# Adafruit_NeoPixel_Ring_24_rev_C.net
KiCad netlist of a schematic drawn in EAGLE
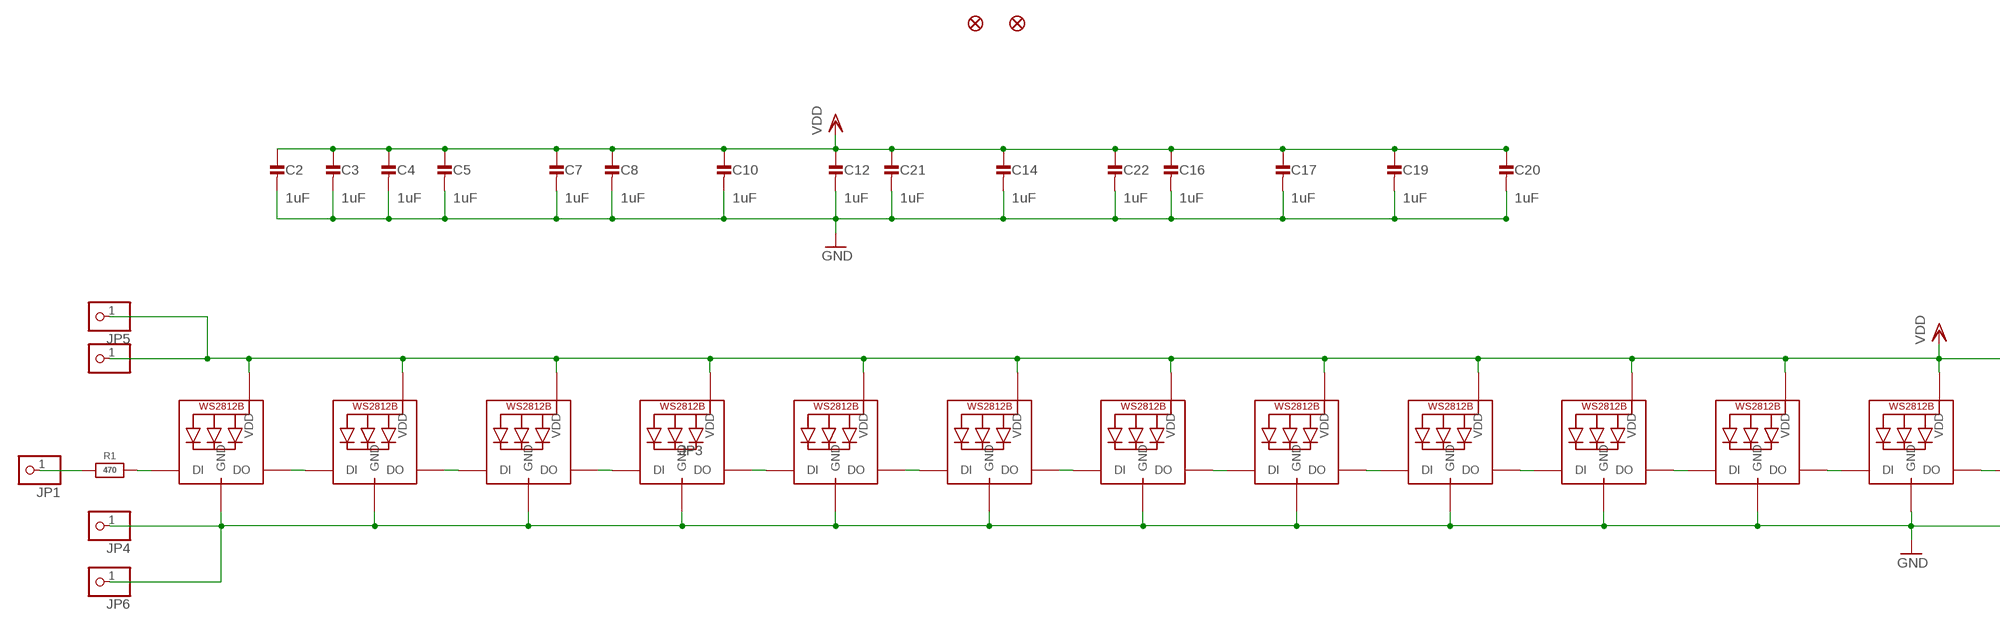
[diagram p0: schematic, sheet 1, part 1 of 2]
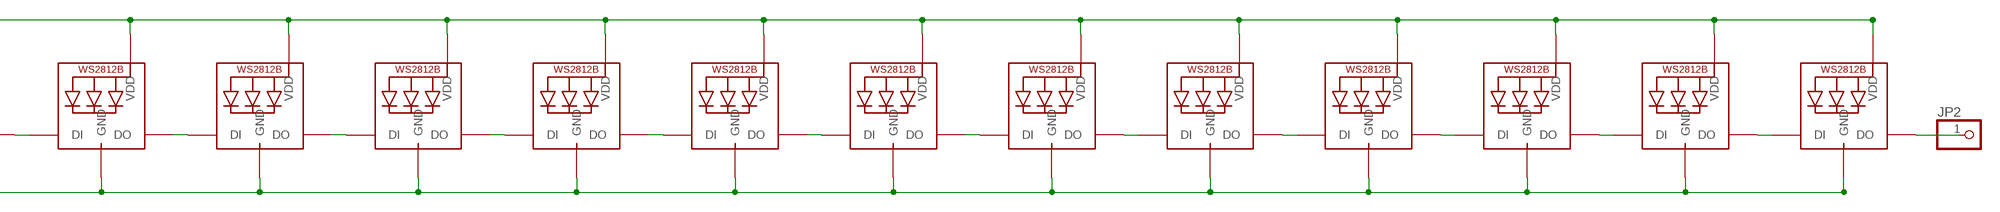
[diagram p1: schematic, sheet 1, part 2 of 2]

(export (version "E")
  (design (tool "Eeschema 10.0.6"))
  (components
    (comp (ref "C2")
      (value "1uF")
      (footprint "eagle-import:0603-NO")
      (libsource (lib "eagle-import") (part "CAP_CERAMIC0603_NO"))
    )
    (comp (ref "C3")
      (value "1uF")
      (footprint "eagle-import:0603-NO")
      (libsource (lib "eagle-import") (part "CAP_CERAMIC0603_NO"))
    )
    (comp (ref "C4")
      (value "1uF")
      (footprint "eagle-import:0603-NO")
      (libsource (lib "eagle-import") (part "CAP_CERAMIC0603_NO"))
    )
    (comp (ref "C5")
      (value "1uF")
      (footprint "eagle-import:0603-NO")
      (libsource (lib "eagle-import") (part "CAP_CERAMIC0603_NO"))
    )
    (comp (ref "C7")
      (value "1uF")
      (footprint "eagle-import:0603-NO")
      (libsource (lib "eagle-import") (part "CAP_CERAMIC0603_NO"))
    )
    (comp (ref "C8")
      (value "1uF")
      (footprint "eagle-import:0603-NO")
      (libsource (lib "eagle-import") (part "CAP_CERAMIC0603_NO"))
    )
    (comp (ref "C10")
      (value "1uF")
      (footprint "eagle-import:0603-NO")
      (libsource (lib "eagle-import") (part "CAP_CERAMIC0603_NO"))
    )
    (comp (ref "C12")
      (value "1uF")
      (footprint "eagle-import:0603-NO")
      (libsource (lib "eagle-import") (part "CAP_CERAMIC0603_NO"))
    )
    (comp (ref "C14")
      (value "1uF")
      (footprint "eagle-import:0603-NO")
      (libsource (lib "eagle-import") (part "CAP_CERAMIC0603_NO"))
    )
    (comp (ref "C16")
      (value "1uF")
      (footprint "eagle-import:0603-NO")
      (libsource (lib "eagle-import") (part "CAP_CERAMIC0603_NO"))
    )
    (comp (ref "C17")
      (value "1uF")
      (footprint "eagle-import:0603-NO")
      (libsource (lib "eagle-import") (part "CAP_CERAMIC0603_NO"))
    )
    (comp (ref "C19")
      (value "1uF")
      (footprint "eagle-import:0603-NO")
      (libsource (lib "eagle-import") (part "CAP_CERAMIC0603_NO"))
    )
    (comp (ref "C20")
      (value "1uF")
      (footprint "eagle-import:0603-NO")
      (libsource (lib "eagle-import") (part "CAP_CERAMIC0603_NO"))
    )
    (comp (ref "C21")
      (value "1uF")
      (footprint "eagle-import:0603-NO")
      (libsource (lib "eagle-import") (part "CAP_CERAMIC0603_NO"))
    )
    (comp (ref "C22")
      (value "1uF")
      (footprint "eagle-import:0603-NO")
      (libsource (lib "eagle-import") (part "CAP_CERAMIC0603_NO"))
    )
    (comp (ref "FID1")
      (value "FIDUCIAL")
      (footprint "eagle-import:FIDUCIAL_1MM")
      (libsource (lib "eagle-import") (part "FIDUCIAL_1MM"))
    )
    (comp (ref "FID2")
      (value "FIDUCIAL")
      (footprint "eagle-import:FIDUCIAL_1MM")
      (libsource (lib "eagle-import") (part "FIDUCIAL_1MM"))
    )
    (comp (ref "JP1")
      (value "PINHD-1X1CB")
      (footprint "eagle-import:1X01-CLEANBIG")
      (libsource (lib "eagle-import") (part "PINHD-1X1CB"))
    )
    (comp (ref "JP2")
      (value "PINHD-1X1CB")
      (footprint "eagle-import:1X01-CLEANBIG")
      (libsource (lib "eagle-import") (part "PINHD-1X1CB"))
    )
    (comp (ref "JP3")
      (value "PINHD-1X1CB")
      (footprint "eagle-import:1X01-CLEANBIG")
      (libsource (lib "eagle-import") (part "PINHD-1X1CB"))
    )
    (comp (ref "JP4")
      (value "PINHD-1X1CB")
      (footprint "eagle-import:1X01-CLEANBIG")
      (libsource (lib "eagle-import") (part "PINHD-1X1CB"))
    )
    (comp (ref "JP5")
      (value "PINHD-1X1CB")
      (footprint "eagle-import:1X01-CLEANBIG")
      (libsource (lib "eagle-import") (part "PINHD-1X1CB"))
    )
    (comp (ref "JP6")
      (value "PINHD-1X1CB")
      (footprint "eagle-import:1X01-CLEANBIG")
      (libsource (lib "eagle-import") (part "PINHD-1X1CB"))
    )
    (comp (ref "LED1")
      (value "WS2812B_5050N")
      (footprint "eagle-import:WS2812B-NARROW")
      (libsource (lib "eagle-import") (part "WS2812B_5050N"))
    )
    (comp (ref "LED2")
      (value "WS2812B_5050N")
      (footprint "eagle-import:WS2812B-NARROW")
      (libsource (lib "eagle-import") (part "WS2812B_5050N"))
    )
    (comp (ref "LED3")
      (value "WS2812B_5050N")
      (footprint "eagle-import:WS2812B-NARROW")
      (libsource (lib "eagle-import") (part "WS2812B_5050N"))
    )
    (comp (ref "LED4")
      (value "WS2812B_5050N")
      (footprint "eagle-import:WS2812B-NARROW")
      (libsource (lib "eagle-import") (part "WS2812B_5050N"))
    )
    (comp (ref "LED5")
      (value "WS2812B_5050N")
      (footprint "eagle-import:WS2812B-NARROW")
      (libsource (lib "eagle-import") (part "WS2812B_5050N"))
    )
    (comp (ref "LED6")
      (value "WS2812B_5050N")
      (footprint "eagle-import:WS2812B-NARROW")
      (libsource (lib "eagle-import") (part "WS2812B_5050N"))
    )
    (comp (ref "LED7")
      (value "WS2812B_5050N")
      (footprint "eagle-import:WS2812B-NARROW")
      (libsource (lib "eagle-import") (part "WS2812B_5050N"))
    )
    (comp (ref "LED8")
      (value "WS2812B_5050N")
      (footprint "eagle-import:WS2812B-NARROW")
      (libsource (lib "eagle-import") (part "WS2812B_5050N"))
    )
    (comp (ref "LED9")
      (value "WS2812B_5050N")
      (footprint "eagle-import:WS2812B-NARROW")
      (libsource (lib "eagle-import") (part "WS2812B_5050N"))
    )
    (comp (ref "LED10")
      (value "WS2812B_5050N")
      (footprint "eagle-import:WS2812B-NARROW")
      (libsource (lib "eagle-import") (part "WS2812B_5050N"))
    )
    (comp (ref "LED11")
      (value "WS2812B_5050N")
      (footprint "eagle-import:WS2812B-NARROW")
      (libsource (lib "eagle-import") (part "WS2812B_5050N"))
    )
    (comp (ref "LED12")
      (value "WS2812B_5050N")
      (footprint "eagle-import:WS2812B-NARROW")
      (libsource (lib "eagle-import") (part "WS2812B_5050N"))
    )
    (comp (ref "LED13")
      (value "WS2812B_5050N")
      (footprint "eagle-import:WS2812B-NARROW")
      (libsource (lib "eagle-import") (part "WS2812B_5050N"))
    )
    (comp (ref "LED14")
      (value "WS2812B_5050N")
      (footprint "eagle-import:WS2812B-NARROW")
      (libsource (lib "eagle-import") (part "WS2812B_5050N"))
    )
    (comp (ref "LED15")
      (value "WS2812B_5050N")
      (footprint "eagle-import:WS2812B-NARROW")
      (libsource (lib "eagle-import") (part "WS2812B_5050N"))
    )
    (comp (ref "LED16")
      (value "WS2812B_5050N")
      (footprint "eagle-import:WS2812B-NARROW")
      (libsource (lib "eagle-import") (part "WS2812B_5050N"))
    )
    (comp (ref "LED17")
      (value "WS2812B_5050N")
      (footprint "eagle-import:WS2812B-NARROW")
      (libsource (lib "eagle-import") (part "WS2812B_5050N"))
    )
    (comp (ref "LED18")
      (value "WS2812B_5050N")
      (footprint "eagle-import:WS2812B-NARROW")
      (libsource (lib "eagle-import") (part "WS2812B_5050N"))
    )
    (comp (ref "LED19")
      (value "WS2812B_5050N")
      (footprint "eagle-import:WS2812B-NARROW")
      (libsource (lib "eagle-import") (part "WS2812B_5050N"))
    )
    (comp (ref "LED20")
      (value "WS2812B_5050N")
      (footprint "eagle-import:WS2812B-NARROW")
      (libsource (lib "eagle-import") (part "WS2812B_5050N"))
    )
    (comp (ref "LED21")
      (value "WS2812B_5050N")
      (footprint "eagle-import:WS2812B-NARROW")
      (libsource (lib "eagle-import") (part "WS2812B_5050N"))
    )
    (comp (ref "LED22")
      (value "WS2812B_5050N")
      (footprint "eagle-import:WS2812B-NARROW")
      (libsource (lib "eagle-import") (part "WS2812B_5050N"))
    )
    (comp (ref "LED23")
      (value "WS2812B_5050N")
      (footprint "eagle-import:WS2812B-NARROW")
      (libsource (lib "eagle-import") (part "WS2812B_5050N"))
    )
    (comp (ref "LED24")
      (value "WS2812B_5050N")
      (footprint "eagle-import:WS2812B-NARROW")
      (libsource (lib "eagle-import") (part "WS2812B_5050N"))
    )
    (comp (ref "R1")
      (value "470")
      (footprint "eagle-import:0603-NO")
      (libsource (lib "eagle-import") (part "RESISTOR_0603_NOOUT"))
    )
  )
  (nets
    (net (code "1") (name "GND") (class "Default")
      (node (ref "C10") (pin "2") (pinfunction "2_2") (pintype "passive"))
      (node (ref "C12") (pin "2") (pinfunction "2_2") (pintype "passive"))
      (node (ref "C14") (pin "2") (pinfunction "2_2") (pintype "passive"))
      (node (ref "C16") (pin "2") (pinfunction "2_2") (pintype "passive"))
      (node (ref "C17") (pin "2") (pinfunction "2_2") (pintype "passive"))
      (node (ref "C19") (pin "2") (pinfunction "2_2") (pintype "passive"))
      (node (ref "C2") (pin "2") (pinfunction "2_2") (pintype "passive"))
      (node (ref "C20") (pin "2") (pinfunction "2_2") (pintype "passive"))
      (node (ref "C21") (pin "2") (pinfunction "2_2") (pintype "passive"))
      (node (ref "C22") (pin "2") (pinfunction "2_2") (pintype "passive"))
      (node (ref "C3") (pin "2") (pinfunction "2_2") (pintype "passive"))
      (node (ref "C4") (pin "2") (pinfunction "2_2") (pintype "passive"))
      (node (ref "C5") (pin "2") (pinfunction "2_2") (pintype "passive"))
      (node (ref "C7") (pin "2") (pinfunction "2_2") (pintype "passive"))
      (node (ref "C8") (pin "2") (pinfunction "2_2") (pintype "passive"))
      (node (ref "JP4") (pin "1") (pinfunction "1_1") (pintype "passive"))
      (node (ref "JP6") (pin "1") (pinfunction "1_1") (pintype "passive"))
      (node (ref "LED1") (pin "3-GND") (pinfunction "GND_3-GND") (pintype "power_in"))
      (node (ref "LED10") (pin "3-GND") (pinfunction "GND_3-GND") (pintype "power_in"))
      (node (ref "LED11") (pin "3-GND") (pinfunction "GND_3-GND") (pintype "power_in"))
      (node (ref "LED12") (pin "3-GND") (pinfunction "GND_3-GND") (pintype "power_in"))
      (node (ref "LED13") (pin "3-GND") (pinfunction "GND_3-GND") (pintype "power_in"))
      (node (ref "LED14") (pin "3-GND") (pinfunction "GND_3-GND") (pintype "power_in"))
      (node (ref "LED15") (pin "3-GND") (pinfunction "GND_3-GND") (pintype "power_in"))
      (node (ref "LED16") (pin "3-GND") (pinfunction "GND_3-GND") (pintype "power_in"))
      (node (ref "LED17") (pin "3-GND") (pinfunction "GND_3-GND") (pintype "power_in"))
      (node (ref "LED18") (pin "3-GND") (pinfunction "GND_3-GND") (pintype "power_in"))
      (node (ref "LED19") (pin "3-GND") (pinfunction "GND_3-GND") (pintype "power_in"))
      (node (ref "LED2") (pin "3-GND") (pinfunction "GND_3-GND") (pintype "power_in"))
      (node (ref "LED20") (pin "3-GND") (pinfunction "GND_3-GND") (pintype "power_in"))
      (node (ref "LED21") (pin "3-GND") (pinfunction "GND_3-GND") (pintype "power_in"))
      (node (ref "LED22") (pin "3-GND") (pinfunction "GND_3-GND") (pintype "power_in"))
      (node (ref "LED23") (pin "3-GND") (pinfunction "GND_3-GND") (pintype "power_in"))
      (node (ref "LED24") (pin "3-GND") (pinfunction "GND_3-GND") (pintype "power_in"))
      (node (ref "LED3") (pin "3-GND") (pinfunction "GND_3-GND") (pintype "power_in"))
      (node (ref "LED4") (pin "3-GND") (pinfunction "GND_3-GND") (pintype "power_in"))
      (node (ref "LED5") (pin "3-GND") (pinfunction "GND_3-GND") (pintype "power_in"))
      (node (ref "LED6") (pin "3-GND") (pinfunction "GND_3-GND") (pintype "power_in"))
      (node (ref "LED7") (pin "3-GND") (pinfunction "GND_3-GND") (pintype "power_in"))
      (node (ref "LED8") (pin "3-GND") (pinfunction "GND_3-GND") (pintype "power_in"))
      (node (ref "LED9") (pin "3-GND") (pinfunction "GND_3-GND") (pintype "power_in"))
    )
    (net (code "2") (name "Net-(JP1-Pad1)") (class "Default")
      (node (ref "JP1") (pin "1") (pinfunction "1_1") (pintype "passive"))
      (node (ref "R1") (pin "1") (pinfunction "1_1") (pintype "passive"))
    )
    (net (code "3") (name "Net-(LED1-DI)") (class "Default")
      (node (ref "LED1") (pin "4-DIN") (pinfunction "DI_4-DIN") (pintype "input"))
      (node (ref "R1") (pin "2") (pinfunction "2_2") (pintype "passive"))
    )
    (net (code "4") (name "Net-(LED1-DO)") (class "Default")
      (node (ref "LED1") (pin "2-DOUT") (pinfunction "DO_2-DOUT") (pintype "output"))
      (node (ref "LED2") (pin "4-DIN") (pinfunction "DI_4-DIN") (pintype "input"))
    )
    (net (code "5") (name "Net-(LED2-DO)") (class "Default")
      (node (ref "LED2") (pin "2-DOUT") (pinfunction "DO_2-DOUT") (pintype "output"))
      (node (ref "LED3") (pin "4-DIN") (pinfunction "DI_4-DIN") (pintype "input"))
    )
    (net (code "6") (name "Net-(LED3-DO)") (class "Default")
      (node (ref "LED3") (pin "2-DOUT") (pinfunction "DO_2-DOUT") (pintype "output"))
      (node (ref "LED4") (pin "4-DIN") (pinfunction "DI_4-DIN") (pintype "input"))
    )
    (net (code "7") (name "Net-(LED4-DO)") (class "Default")
      (node (ref "LED4") (pin "2-DOUT") (pinfunction "DO_2-DOUT") (pintype "output"))
      (node (ref "LED5") (pin "4-DIN") (pinfunction "DI_4-DIN") (pintype "input"))
    )
    (net (code "8") (name "Net-(LED5-DO)") (class "Default")
      (node (ref "LED5") (pin "2-DOUT") (pinfunction "DO_2-DOUT") (pintype "output"))
      (node (ref "LED6") (pin "4-DIN") (pinfunction "DI_4-DIN") (pintype "input"))
    )
    (net (code "9") (name "Net-(LED6-DO)") (class "Default")
      (node (ref "LED6") (pin "2-DOUT") (pinfunction "DO_2-DOUT") (pintype "output"))
      (node (ref "LED7") (pin "4-DIN") (pinfunction "DI_4-DIN") (pintype "input"))
    )
    (net (code "10") (name "Net-(LED7-DO)") (class "Default")
      (node (ref "LED7") (pin "2-DOUT") (pinfunction "DO_2-DOUT") (pintype "output"))
      (node (ref "LED8") (pin "4-DIN") (pinfunction "DI_4-DIN") (pintype "input"))
    )
    (net (code "11") (name "Net-(LED8-DO)") (class "Default")
      (node (ref "LED8") (pin "2-DOUT") (pinfunction "DO_2-DOUT") (pintype "output"))
      (node (ref "LED9") (pin "4-DIN") (pinfunction "DI_4-DIN") (pintype "input"))
    )
    (net (code "12") (name "Net-(LED10-DI)") (class "Default")
      (node (ref "LED10") (pin "4-DIN") (pinfunction "DI_4-DIN") (pintype "input"))
      (node (ref "LED9") (pin "2-DOUT") (pinfunction "DO_2-DOUT") (pintype "output"))
    )
    (net (code "13") (name "Net-(LED10-DO)") (class "Default")
      (node (ref "LED10") (pin "2-DOUT") (pinfunction "DO_2-DOUT") (pintype "output"))
      (node (ref "LED11") (pin "4-DIN") (pinfunction "DI_4-DIN") (pintype "input"))
    )
    (net (code "14") (name "Net-(LED11-DO)") (class "Default")
      (node (ref "LED11") (pin "2-DOUT") (pinfunction "DO_2-DOUT") (pintype "output"))
      (node (ref "LED12") (pin "4-DIN") (pinfunction "DI_4-DIN") (pintype "input"))
    )
    (net (code "15") (name "Net-(LED12-DO)") (class "Default")
      (node (ref "LED12") (pin "2-DOUT") (pinfunction "DO_2-DOUT") (pintype "output"))
      (node (ref "LED13") (pin "4-DIN") (pinfunction "DI_4-DIN") (pintype "input"))
    )
    (net (code "16") (name "Net-(LED13-DO)") (class "Default")
      (node (ref "LED13") (pin "2-DOUT") (pinfunction "DO_2-DOUT") (pintype "output"))
      (node (ref "LED14") (pin "4-DIN") (pinfunction "DI_4-DIN") (pintype "input"))
    )
    (net (code "17") (name "Net-(LED14-DO)") (class "Default")
      (node (ref "LED14") (pin "2-DOUT") (pinfunction "DO_2-DOUT") (pintype "output"))
      (node (ref "LED15") (pin "4-DIN") (pinfunction "DI_4-DIN") (pintype "input"))
    )
    (net (code "18") (name "Net-(LED15-DO)") (class "Default")
      (node (ref "LED15") (pin "2-DOUT") (pinfunction "DO_2-DOUT") (pintype "output"))
      (node (ref "LED16") (pin "4-DIN") (pinfunction "DI_4-DIN") (pintype "input"))
    )
    (net (code "19") (name "Net-(LED16-DO)") (class "Default")
      (node (ref "LED16") (pin "2-DOUT") (pinfunction "DO_2-DOUT") (pintype "output"))
      (node (ref "LED17") (pin "4-DIN") (pinfunction "DI_4-DIN") (pintype "input"))
    )
    (net (code "20") (name "Net-(LED17-DO)") (class "Default")
      (node (ref "LED17") (pin "2-DOUT") (pinfunction "DO_2-DOUT") (pintype "output"))
      (node (ref "LED18") (pin "4-DIN") (pinfunction "DI_4-DIN") (pintype "input"))
    )
    (net (code "21") (name "Net-(LED18-DO)") (class "Default")
      (node (ref "LED18") (pin "2-DOUT") (pinfunction "DO_2-DOUT") (pintype "output"))
      (node (ref "LED19") (pin "4-DIN") (pinfunction "DI_4-DIN") (pintype "input"))
    )
    (net (code "22") (name "Net-(LED19-DO)") (class "Default")
      (node (ref "LED19") (pin "2-DOUT") (pinfunction "DO_2-DOUT") (pintype "output"))
      (node (ref "LED20") (pin "4-DIN") (pinfunction "DI_4-DIN") (pintype "input"))
    )
    (net (code "23") (name "Net-(LED20-DO)") (class "Default")
      (node (ref "LED20") (pin "2-DOUT") (pinfunction "DO_2-DOUT") (pintype "output"))
      (node (ref "LED21") (pin "4-DIN") (pinfunction "DI_4-DIN") (pintype "input"))
    )
    (net (code "24") (name "Net-(LED21-DO)") (class "Default")
      (node (ref "LED21") (pin "2-DOUT") (pinfunction "DO_2-DOUT") (pintype "output"))
      (node (ref "LED22") (pin "4-DIN") (pinfunction "DI_4-DIN") (pintype "input"))
    )
    (net (code "25") (name "Net-(LED22-DO)") (class "Default")
      (node (ref "LED22") (pin "2-DOUT") (pinfunction "DO_2-DOUT") (pintype "output"))
      (node (ref "LED23") (pin "4-DIN") (pinfunction "DI_4-DIN") (pintype "input"))
    )
    (net (code "26") (name "Net-(LED23-DO)") (class "Default")
      (node (ref "LED23") (pin "2-DOUT") (pinfunction "DO_2-DOUT") (pintype "output"))
      (node (ref "LED24") (pin "4-DIN") (pinfunction "DI_4-DIN") (pintype "input"))
    )
    (net (code "27") (name "Net-(LED24-DO)") (class "Default")
      (node (ref "JP2") (pin "1") (pinfunction "1_1") (pintype "passive"))
      (node (ref "LED24") (pin "2-DOUT") (pinfunction "DO_2-DOUT") (pintype "output"))
    )
    (net (code "28") (name "VDD") (class "Default")
      (node (ref "C10") (pin "1") (pinfunction "1_1") (pintype "passive"))
      (node (ref "C12") (pin "1") (pinfunction "1_1") (pintype "passive"))
      (node (ref "C14") (pin "1") (pinfunction "1_1") (pintype "passive"))
      (node (ref "C16") (pin "1") (pinfunction "1_1") (pintype "passive"))
      (node (ref "C17") (pin "1") (pinfunction "1_1") (pintype "passive"))
      (node (ref "C19") (pin "1") (pinfunction "1_1") (pintype "passive"))
      (node (ref "C2") (pin "1") (pinfunction "1_1") (pintype "passive"))
      (node (ref "C20") (pin "1") (pinfunction "1_1") (pintype "passive"))
      (node (ref "C21") (pin "1") (pinfunction "1_1") (pintype "passive"))
      (node (ref "C22") (pin "1") (pinfunction "1_1") (pintype "passive"))
      (node (ref "C3") (pin "1") (pinfunction "1_1") (pintype "passive"))
      (node (ref "C4") (pin "1") (pinfunction "1_1") (pintype "passive"))
      (node (ref "C5") (pin "1") (pinfunction "1_1") (pintype "passive"))
      (node (ref "C7") (pin "1") (pinfunction "1_1") (pintype "passive"))
      (node (ref "C8") (pin "1") (pinfunction "1_1") (pintype "passive"))
      (node (ref "JP3") (pin "1") (pinfunction "1_1") (pintype "passive"))
      (node (ref "JP5") (pin "1") (pinfunction "1_1") (pintype "passive"))
      (node (ref "LED1") (pin "1-VDD") (pinfunction "VDD_1-VDD") (pintype "power_in"))
      (node (ref "LED10") (pin "1-VDD") (pinfunction "VDD_1-VDD") (pintype "power_in"))
      (node (ref "LED11") (pin "1-VDD") (pinfunction "VDD_1-VDD") (pintype "power_in"))
      (node (ref "LED12") (pin "1-VDD") (pinfunction "VDD_1-VDD") (pintype "power_in"))
      (node (ref "LED13") (pin "1-VDD") (pinfunction "VDD_1-VDD") (pintype "power_in"))
      (node (ref "LED14") (pin "1-VDD") (pinfunction "VDD_1-VDD") (pintype "power_in"))
      (node (ref "LED15") (pin "1-VDD") (pinfunction "VDD_1-VDD") (pintype "power_in"))
      (node (ref "LED16") (pin "1-VDD") (pinfunction "VDD_1-VDD") (pintype "power_in"))
      (node (ref "LED17") (pin "1-VDD") (pinfunction "VDD_1-VDD") (pintype "power_in"))
      (node (ref "LED18") (pin "1-VDD") (pinfunction "VDD_1-VDD") (pintype "power_in"))
      (node (ref "LED19") (pin "1-VDD") (pinfunction "VDD_1-VDD") (pintype "power_in"))
      (node (ref "LED2") (pin "1-VDD") (pinfunction "VDD_1-VDD") (pintype "power_in"))
      (node (ref "LED20") (pin "1-VDD") (pinfunction "VDD_1-VDD") (pintype "power_in"))
      (node (ref "LED21") (pin "1-VDD") (pinfunction "VDD_1-VDD") (pintype "power_in"))
      (node (ref "LED22") (pin "1-VDD") (pinfunction "VDD_1-VDD") (pintype "power_in"))
      (node (ref "LED23") (pin "1-VDD") (pinfunction "VDD_1-VDD") (pintype "power_in"))
      (node (ref "LED24") (pin "1-VDD") (pinfunction "VDD_1-VDD") (pintype "power_in"))
      (node (ref "LED3") (pin "1-VDD") (pinfunction "VDD_1-VDD") (pintype "power_in"))
      (node (ref "LED4") (pin "1-VDD") (pinfunction "VDD_1-VDD") (pintype "power_in"))
      (node (ref "LED5") (pin "1-VDD") (pinfunction "VDD_1-VDD") (pintype "power_in"))
      (node (ref "LED6") (pin "1-VDD") (pinfunction "VDD_1-VDD") (pintype "power_in"))
      (node (ref "LED7") (pin "1-VDD") (pinfunction "VDD_1-VDD") (pintype "power_in"))
      (node (ref "LED8") (pin "1-VDD") (pinfunction "VDD_1-VDD") (pintype "power_in"))
      (node (ref "LED9") (pin "1-VDD") (pinfunction "VDD_1-VDD") (pintype "power_in"))
    )
  )
)
